# Sheet2.net
KiCad netlist of a schematic drawn in Altium Designer
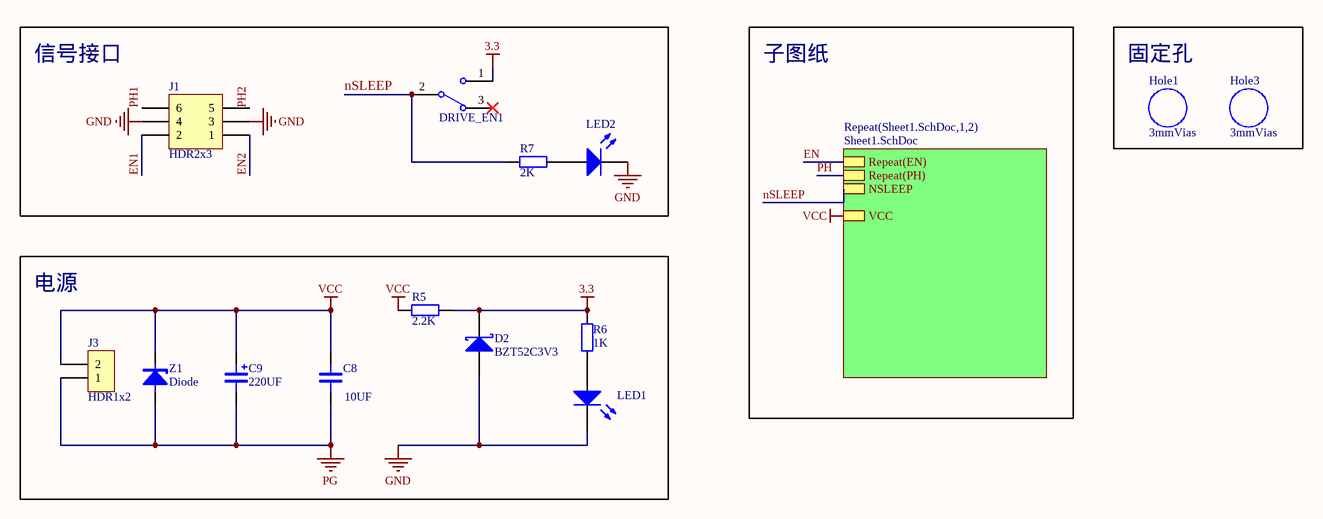
[diagram p0: Sheet2.SchDoc]

(export (version "E")
  (design (tool "Eeschema 10.0.6"))
  (components
    (comp (ref "C8")
      (value "10UF")
      (footprint "0603")
      (description "Capacitor")
      (libsource (lib "General") (part "CAP"))
    )
    (comp (ref "C9")
      (value "220UF")
      (footprint "DIP-EC3.5X8X11.5")
      (description "Tantalum Capacitor")
      (libsource (lib "General") (part "CAP-TANTALUM"))
    )
    (comp (ref "D2")
      (value "BZT52C3V3")
      (footprint "SOD-123")
      (description "Schottky Rectifier")
      (fields (field (name "PUBLISHER") "Altium Limited"))
      (libsource (lib "Miscellaneous Devices") (part "Diode 18TQ045"))
    )
    (comp (ref "DRIVE_EN1")
      (value "SW-SPDT")
      (footprint "ss12d10")
      (description "SPDT Subminiature Toggle Switch, Right Angle Mounting, Vertical Actuation")
      (fields (field (name "PUBLISHER") "Altium Limited"))
      (libsource (lib "Miscellaneous Devices") (part "SW-SPDT"))
    )
    (comp (ref "Hole1") (value "3mmVias") (footprint "3mm") (libsource (lib "General") (part "3mmVias")))
    (comp (ref "Hole3") (value "3mmVias") (footprint "3mm") (libsource (lib "General") (part "3mmVias")))
    (comp (ref "J1")
      (value "HDR2x3")
      (footprint "pin_2*3")
      (description "Connector")
      (libsource (lib "General") (part "HDR2x3"))
    )
    (comp (ref "J3")
      (value "HDR1x2")
      (footprint "TX30_接口")
      (description "Connector")
      (libsource (lib "General") (part "HDR1x2"))
    )
    (comp (ref "LED1")
      (value "LED0")
      (footprint "0603-led")
      (description "Typical INFRARED GaAs LED")
      (fields (field (name "PUBLISHER") "Altium Limited"))
      (libsource (lib "Miscellaneous Devices") (part "LED0"))
    )
    (comp (ref "LED2")
      (value "LED0")
      (footprint "0603-led")
      (description "Typical INFRARED GaAs LED")
      (fields (field (name "PUBLISHER") "Altium Limited"))
      (libsource (lib "Miscellaneous Devices") (part "LED0"))
    )
    (comp (ref "R5")
      (value "2.2K")
      (footprint "0603")
      (description "Resistor")
      (libsource (lib "General") (part "RES"))
    )
    (comp (ref "R6")
      (value "1K")
      (footprint "0603")
      (description "Resistor")
      (libsource (lib "") (part "RES_1"))
    )
    (comp (ref "R7")
      (value "2K")
      (footprint "0603")
      (description "Resistor")
      (libsource (lib "General") (part "RES"))
    )
    (comp (ref "Z1")
      (value "Diode")
      (footprint "SMA")
      (description "Zener Diode")
      (libsource (lib "General") (part "Diode"))
    )
  )
  (nets
    (net (code "2") (name "/EN1") (class "Default")
      (node (ref "J1") (pin "2") (pinfunction "2_2") (pintype "passive"))
    )
    (net (code "3") (name "/EN2") (class "Default")
      (node (ref "J1") (pin "1") (pinfunction "1_1") (pintype "passive"))
    )
    (net (code "5") (name "/PH1") (class "Default")
      (node (ref "J1") (pin "6") (pinfunction "6_6") (pintype "passive"))
    )
    (net (code "6") (name "/PH2") (class "Default")
      (node (ref "J1") (pin "5") (pinfunction "5_5") (pintype "passive"))
    )
    (net (code "7") (name "/nSLEEP") (class "Default")
      (node (ref "DRIVE_EN1") (pin "2") (pinfunction "2_2") (pintype "passive"))
      (node (ref "R7") (pin "2") (pinfunction "2_2") (pintype "passive"))
    )
    (net (code "8") (name "3.3") (class "Default")
      (node (ref "D2") (pin "1") (pinfunction "K_1") (pintype "passive"))
      (node (ref "DRIVE_EN1") (pin "1") (pinfunction "1_1") (pintype "passive"))
      (node (ref "R5") (pin "1") (pinfunction "1_1") (pintype "passive"))
      (node (ref "R6") (pin "1") (pinfunction "1_1") (pintype "passive"))
    )
    (net (code "9") (name "GND") (class "Default")
      (node (ref "D2") (pin "3") (pinfunction "A_3") (pintype "passive"))
      (node (ref "J1") (pin "3") (pinfunction "3_3") (pintype "passive"))
      (node (ref "J1") (pin "4") (pinfunction "4_4") (pintype "passive"))
      (node (ref "LED1") (pin "2") (pinfunction "K_2") (pintype "passive"))
      (node (ref "LED2") (pin "2") (pinfunction "K_2") (pintype "passive"))
    )
    (net (code "10") (name "Net-(LED1-A)") (class "Default")
      (node (ref "LED1") (pin "1") (pinfunction "A_1") (pintype "passive"))
      (node (ref "R6") (pin "2") (pinfunction "2_2") (pintype "passive"))
    )
    (net (code "11") (name "Net-(LED2-A)") (class "Default")
      (node (ref "LED2") (pin "1") (pinfunction "A_1") (pintype "passive"))
      (node (ref "R7") (pin "1") (pinfunction "1_1") (pintype "passive"))
    )
    (net (code "12") (name "PG") (class "Default")
      (node (ref "C8") (pin "1") (pinfunction "1_1") (pintype "passive"))
      (node (ref "C9") (pin "2") (pinfunction "2_2") (pintype "passive"))
      (node (ref "J3") (pin "1") (pinfunction "1_1") (pintype "passive"))
      (node (ref "Z1") (pin "1") (pinfunction "A_1") (pintype "passive"))
    )
    (net (code "13") (name "VCC") (class "Default")
      (node (ref "C8") (pin "2") (pinfunction "2_2") (pintype "passive"))
      (node (ref "C9") (pin "1") (pinfunction "1_1") (pintype "passive"))
      (node (ref "J3") (pin "2") (pinfunction "2_2") (pintype "passive"))
      (node (ref "R5") (pin "2") (pinfunction "2_2") (pintype "passive"))
      (node (ref "Z1") (pin "2") (pinfunction "C_2") (pintype "passive"))
    )
    (net (code "14") (name "unconnected-(DRIVE_EN1-Pad3)") (class "Default")
      (node (ref "DRIVE_EN1") (pin "3") (pinfunction "3_3") (pintype "passive+no_connect"))
    )
  )
)
